# PCB_1.net
KiCad netlist of a schematic drawn in EAGLE
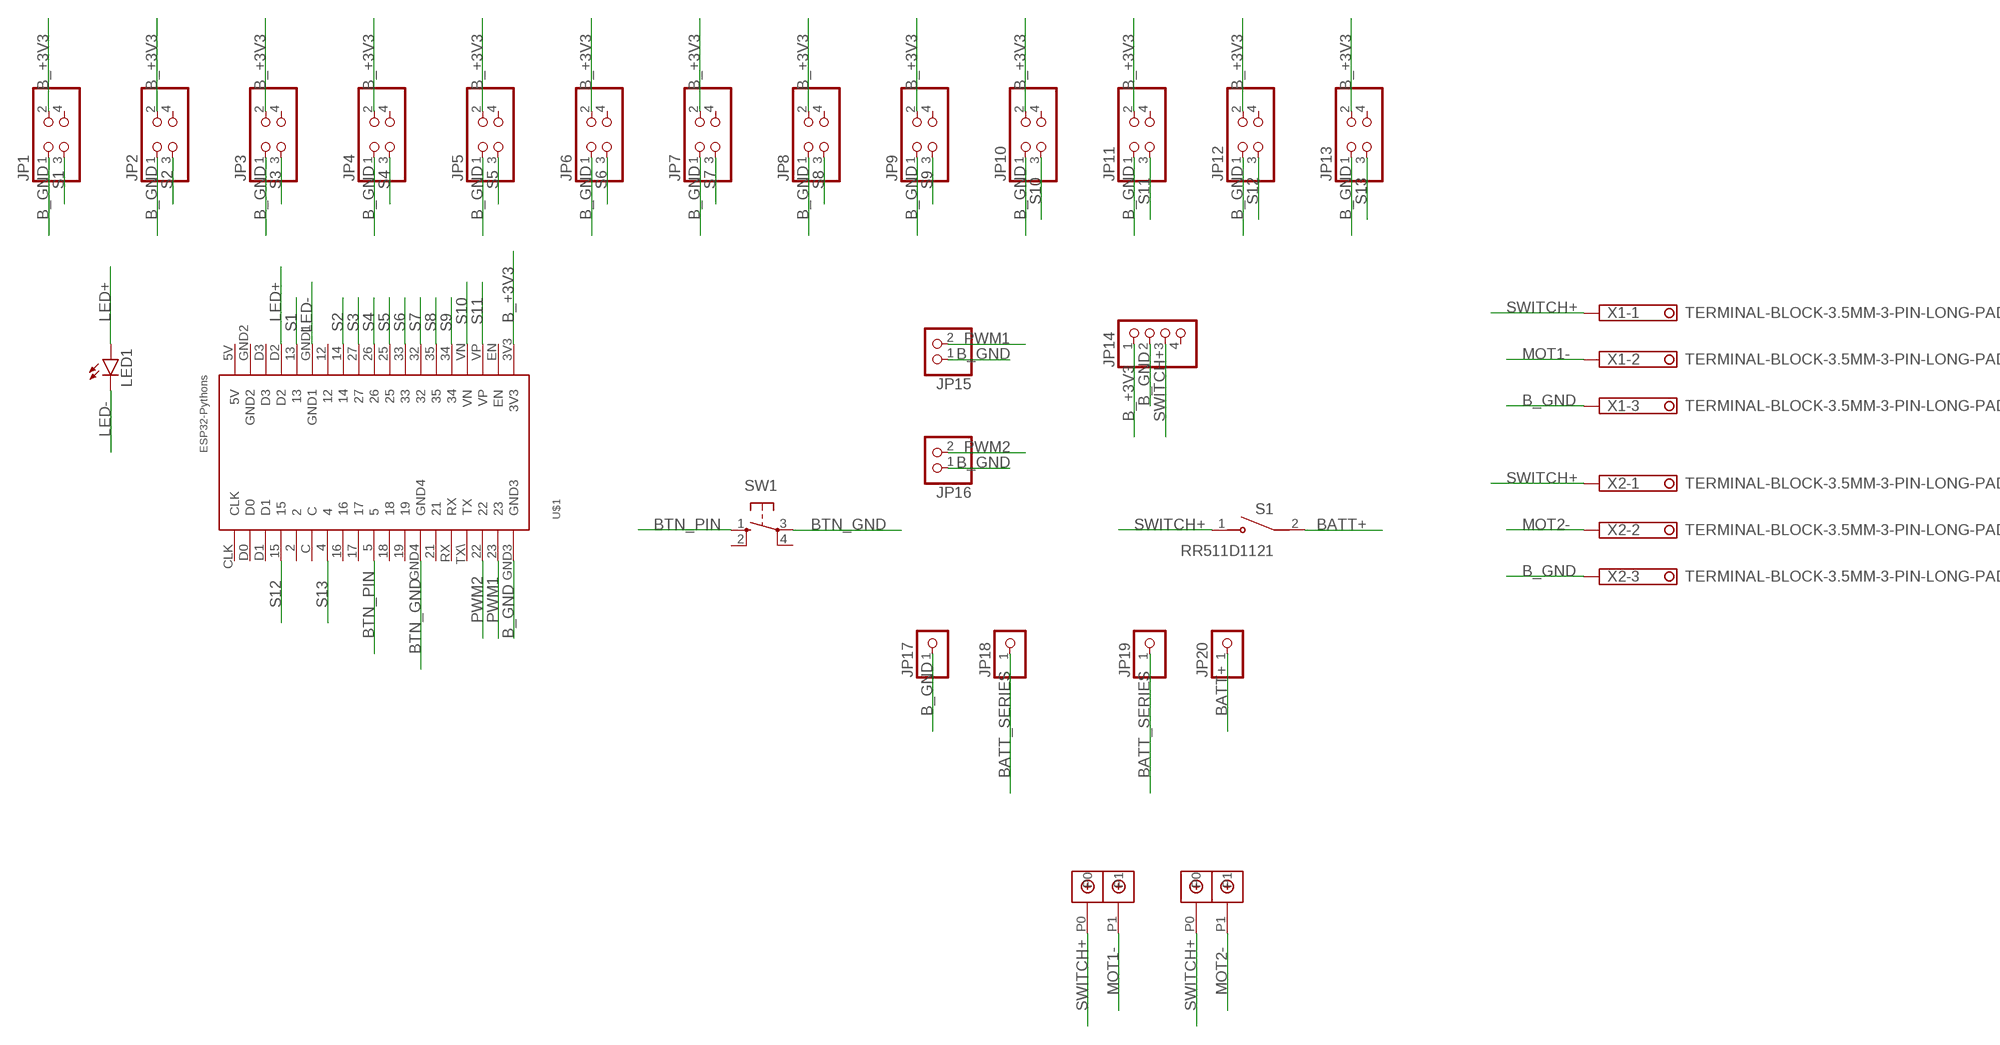
[diagram p0: schematic, sheet 1]

(export (version "E")
  (design (tool "Eeschema 10.0.6"))
  (components
    (comp (ref "JP1")
      (value "PINHD-2X2")
      (footprint "eagle-import:2X02")
      (libsource (lib "eagle-import") (part "PINHD-2X2"))
    )
    (comp (ref "JP2")
      (value "PINHD-2X2")
      (footprint "eagle-import:2X02")
      (libsource (lib "eagle-import") (part "PINHD-2X2"))
    )
    (comp (ref "JP3")
      (value "PINHD-2X2")
      (footprint "eagle-import:2X02")
      (libsource (lib "eagle-import") (part "PINHD-2X2"))
    )
    (comp (ref "JP4")
      (value "PINHD-2X2")
      (footprint "eagle-import:2X02")
      (libsource (lib "eagle-import") (part "PINHD-2X2"))
    )
    (comp (ref "JP5")
      (value "PINHD-2X2")
      (footprint "eagle-import:2X02")
      (libsource (lib "eagle-import") (part "PINHD-2X2"))
    )
    (comp (ref "JP6")
      (value "PINHD-2X2")
      (footprint "eagle-import:2X02")
      (libsource (lib "eagle-import") (part "PINHD-2X2"))
    )
    (comp (ref "JP7")
      (value "PINHD-2X2")
      (footprint "eagle-import:2X02")
      (libsource (lib "eagle-import") (part "PINHD-2X2"))
    )
    (comp (ref "JP8")
      (value "PINHD-2X2")
      (footprint "eagle-import:2X02")
      (libsource (lib "eagle-import") (part "PINHD-2X2"))
    )
    (comp (ref "JP9")
      (value "PINHD-2X2")
      (footprint "eagle-import:2X02")
      (libsource (lib "eagle-import") (part "PINHD-2X2"))
    )
    (comp (ref "JP10")
      (value "PINHD-2X2")
      (footprint "eagle-import:2X02")
      (libsource (lib "eagle-import") (part "PINHD-2X2"))
    )
    (comp (ref "JP11")
      (value "PINHD-2X2")
      (footprint "eagle-import:2X02")
      (libsource (lib "eagle-import") (part "PINHD-2X2"))
    )
    (comp (ref "JP12")
      (value "PINHD-2X2")
      (footprint "eagle-import:2X02")
      (libsource (lib "eagle-import") (part "PINHD-2X2"))
    )
    (comp (ref "JP13")
      (value "PINHD-2X2")
      (footprint "eagle-import:2X02")
      (libsource (lib "eagle-import") (part "PINHD-2X2"))
    )
    (comp (ref "JP14")
      (value "PINHD-1X4")
      (footprint "eagle-import:1X04")
      (libsource (lib "eagle-import") (part "PINHD-1X4"))
    )
    (comp (ref "JP15")
      (value "PINHD-1X2")
      (footprint "eagle-import:1X02")
      (libsource (lib "eagle-import") (part "PINHD-1X2"))
    )
    (comp (ref "JP16")
      (value "PINHD-1X2")
      (footprint "eagle-import:1X02")
      (libsource (lib "eagle-import") (part "PINHD-1X2"))
    )
    (comp (ref "JP17")
      (value "PINHD-1X1")
      (footprint "eagle-import:1X01")
      (libsource (lib "eagle-import") (part "PINHD-1X1"))
    )
    (comp (ref "JP18")
      (value "PINHD-1X1")
      (footprint "eagle-import:1X01")
      (libsource (lib "eagle-import") (part "PINHD-1X1"))
    )
    (comp (ref "JP19")
      (value "PINHD-1X1")
      (footprint "eagle-import:1X01")
      (libsource (lib "eagle-import") (part "PINHD-1X1"))
    )
    (comp (ref "JP20")
      (value "PINHD-1X1")
      (footprint "eagle-import:1X01")
      (libsource (lib "eagle-import") (part "PINHD-1X1"))
    )
    (comp (ref "LED1")
      (value "LED5MM")
      (footprint "eagle-import:LED5MM")
      (libsource (lib "eagle-import") (part "LED5MM"))
    )
    (comp (ref "S1")
      (value "RR511D1121")
      (footprint "eagle-import:E-SWITCH_RR511D1121")
      (fields (field (name "MF") "E-Switch"))
      (libsource (lib "eagle-import") (part "RR511D1121"))
    )
    (comp (ref "SW1")
      (value "10-XX")
      (footprint "eagle-import:B3F-10XX")
      (libsource (lib "eagle-import") (part "10-XX"))
    )
    (comp (ref "U$1")
      (value "ESP32DEVKITV1")
      (footprint "eagle-import:ESP32-DEVKITV1")
      (libsource (lib "eagle-import") (part "ESP32DEVKITV1"))
    )
    (comp (ref "U$2")
      (value "DBCONN-1X2")
      (footprint "eagle-import:DBCONN-1X2")
      (libsource (lib "eagle-import") (part "DBCONN-1X2"))
    )
    (comp (ref "U$3")
      (value "DBCONN-1X2")
      (footprint "eagle-import:DBCONN-1X2")
      (libsource (lib "eagle-import") (part "DBCONN-1X2"))
    )
    (comp (ref "X1")
      (value "TERMINAL-BLOCK-3.5MM-3-PIN-LONG-PAD")
      (footprint "eagle-import:TERMINAL-BLOCK-3-PIN-3.5MM-LONG-PAD")
      (libsource (lib "eagle-import") (part "TERMINAL-BLOCK-3.5MM-3-PIN-LONG-PAD"))
    )
    (comp (ref "X2")
      (value "TERMINAL-BLOCK-3.5MM-3-PIN-LONG-PAD")
      (footprint "eagle-import:TERMINAL-BLOCK-3-PIN-3.5MM-LONG-PAD")
      (libsource (lib "eagle-import") (part "TERMINAL-BLOCK-3.5MM-3-PIN-LONG-PAD"))
    )
  )
  (nets
    (net (code "1") (name "/BATT+") (class "Default")
      (node (ref "JP20") (pin "1") (pinfunction "1_1") (pintype "passive"))
      (node (ref "S1") (pin "2") (pinfunction "COM_2") (pintype "passive"))
    )
    (net (code "2") (name "/BATT_SERIES") (class "Default")
      (node (ref "JP18") (pin "1") (pinfunction "1_1") (pintype "passive"))
      (node (ref "JP19") (pin "1") (pinfunction "1_1") (pintype "passive"))
    )
    (net (code "3") (name "/BTN_GND") (class "Default")
      (node (ref "SW1") (pin "3") (pinfunction "P_3") (pintype "passive"))
      (node (ref "U$1") (pin "GND4") (pinfunction "GND4_GND4") (pintype "bidirectional"))
    )
    (net (code "4") (name "/BTN_PIN") (class "Default")
      (node (ref "SW1") (pin "1") (pinfunction "S_1") (pintype "passive"))
      (node (ref "U$1") (pin "5") (pinfunction "5_5") (pintype "bidirectional"))
    )
    (net (code "5") (name "/B_+3V3") (class "Default")
      (node (ref "JP1") (pin "2") (pinfunction "2_2") (pintype "passive"))
      (node (ref "JP10") (pin "2") (pinfunction "2_2") (pintype "passive"))
      (node (ref "JP11") (pin "2") (pinfunction "2_2") (pintype "passive"))
      (node (ref "JP12") (pin "2") (pinfunction "2_2") (pintype "passive"))
      (node (ref "JP13") (pin "2") (pinfunction "2_2") (pintype "passive"))
      (node (ref "JP14") (pin "1") (pinfunction "1_1") (pintype "passive"))
      (node (ref "JP2") (pin "2") (pinfunction "2_2") (pintype "passive"))
      (node (ref "JP3") (pin "2") (pinfunction "2_2") (pintype "passive"))
      (node (ref "JP4") (pin "2") (pinfunction "2_2") (pintype "passive"))
      (node (ref "JP5") (pin "2") (pinfunction "2_2") (pintype "passive"))
      (node (ref "JP6") (pin "2") (pinfunction "2_2") (pintype "passive"))
      (node (ref "JP7") (pin "2") (pinfunction "2_2") (pintype "passive"))
      (node (ref "JP8") (pin "2") (pinfunction "2_2") (pintype "passive"))
      (node (ref "JP9") (pin "2") (pinfunction "2_2") (pintype "passive"))
      (node (ref "U$1") (pin "3V3") (pinfunction "3V3_3V3") (pintype "bidirectional"))
    )
    (net (code "6") (name "/B_GND") (class "Default")
      (node (ref "JP1") (pin "1") (pinfunction "1_1") (pintype "passive"))
      (node (ref "JP10") (pin "1") (pinfunction "1_1") (pintype "passive"))
      (node (ref "JP11") (pin "1") (pinfunction "1_1") (pintype "passive"))
      (node (ref "JP12") (pin "1") (pinfunction "1_1") (pintype "passive"))
      (node (ref "JP13") (pin "1") (pinfunction "1_1") (pintype "passive"))
      (node (ref "JP14") (pin "2") (pinfunction "2_2") (pintype "passive"))
      (node (ref "JP15") (pin "1") (pinfunction "1_1") (pintype "passive"))
      (node (ref "JP16") (pin "1") (pinfunction "1_1") (pintype "passive"))
      (node (ref "JP17") (pin "1") (pinfunction "1_1") (pintype "passive"))
      (node (ref "JP2") (pin "1") (pinfunction "1_1") (pintype "passive"))
      (node (ref "JP3") (pin "1") (pinfunction "1_1") (pintype "passive"))
      (node (ref "JP4") (pin "1") (pinfunction "1_1") (pintype "passive"))
      (node (ref "JP5") (pin "1") (pinfunction "1_1") (pintype "passive"))
      (node (ref "JP6") (pin "1") (pinfunction "1_1") (pintype "passive"))
      (node (ref "JP7") (pin "1") (pinfunction "1_1") (pintype "passive"))
      (node (ref "JP8") (pin "1") (pinfunction "1_1") (pintype "passive"))
      (node (ref "JP9") (pin "1") (pinfunction "1_1") (pintype "passive"))
      (node (ref "U$1") (pin "GND3") (pinfunction "GND3_GND3") (pintype "bidirectional"))
      (node (ref "X1") (pin "3") (pinfunction "K_3") (pintype "passive"))
      (node (ref "X2") (pin "3") (pinfunction "K_3") (pintype "passive"))
    )
    (net (code "7") (name "/LED+") (class "Default")
      (node (ref "LED1") (pin "A") (pinfunction "A_A") (pintype "passive"))
      (node (ref "U$1") (pin "D2") (pinfunction "D2_D2") (pintype "bidirectional"))
    )
    (net (code "8") (name "/LED-") (class "Default")
      (node (ref "LED1") (pin "K") (pinfunction "C_K") (pintype "passive"))
      (node (ref "U$1") (pin "GND1") (pinfunction "GND1_GND1") (pintype "bidirectional"))
    )
    (net (code "9") (name "/MOT1-") (class "Default")
      (node (ref "U$2") (pin "P1") (pinfunction "P1_P1") (pintype "bidirectional"))
      (node (ref "X1") (pin "2") (pinfunction "K_2") (pintype "passive"))
    )
    (net (code "10") (name "/MOT2-") (class "Default")
      (node (ref "U$3") (pin "P1") (pinfunction "P1_P1") (pintype "bidirectional"))
      (node (ref "X2") (pin "2") (pinfunction "K_2") (pintype "passive"))
    )
    (net (code "11") (name "/PWM1") (class "Default")
      (node (ref "JP15") (pin "2") (pinfunction "2_2") (pintype "passive"))
      (node (ref "U$1") (pin "23") (pinfunction "23_23") (pintype "bidirectional"))
    )
    (net (code "12") (name "/PWM2") (class "Default")
      (node (ref "JP16") (pin "2") (pinfunction "2_2") (pintype "passive"))
      (node (ref "U$1") (pin "22") (pinfunction "22_22") (pintype "bidirectional"))
    )
    (net (code "13") (name "/S1") (class "Default")
      (node (ref "JP1") (pin "3") (pinfunction "3_3") (pintype "passive"))
      (node (ref "U$1") (pin "13") (pinfunction "13_13") (pintype "bidirectional"))
    )
    (net (code "14") (name "/S2") (class "Default")
      (node (ref "JP2") (pin "3") (pinfunction "3_3") (pintype "passive"))
      (node (ref "U$1") (pin "14") (pinfunction "14_14") (pintype "bidirectional"))
    )
    (net (code "15") (name "/S3") (class "Default")
      (node (ref "JP3") (pin "3") (pinfunction "3_3") (pintype "passive"))
      (node (ref "U$1") (pin "27") (pinfunction "27_27") (pintype "bidirectional"))
    )
    (net (code "16") (name "/S4") (class "Default")
      (node (ref "JP4") (pin "3") (pinfunction "3_3") (pintype "passive"))
      (node (ref "U$1") (pin "26") (pinfunction "26_26") (pintype "bidirectional"))
    )
    (net (code "17") (name "/S5") (class "Default")
      (node (ref "JP5") (pin "3") (pinfunction "3_3") (pintype "passive"))
      (node (ref "U$1") (pin "25") (pinfunction "25_25") (pintype "bidirectional"))
    )
    (net (code "18") (name "/S6") (class "Default")
      (node (ref "JP6") (pin "3") (pinfunction "3_3") (pintype "passive"))
      (node (ref "U$1") (pin "33") (pinfunction "33_33") (pintype "bidirectional"))
    )
    (net (code "19") (name "/S7") (class "Default")
      (node (ref "JP7") (pin "3") (pinfunction "3_3") (pintype "passive"))
      (node (ref "U$1") (pin "32") (pinfunction "32_32") (pintype "bidirectional"))
    )
    (net (code "20") (name "/S8") (class "Default")
      (node (ref "JP8") (pin "3") (pinfunction "3_3") (pintype "passive"))
      (node (ref "U$1") (pin "35") (pinfunction "35_35") (pintype "bidirectional"))
    )
    (net (code "21") (name "/S9") (class "Default")
      (node (ref "JP9") (pin "3") (pinfunction "3_3") (pintype "passive"))
      (node (ref "U$1") (pin "34") (pinfunction "34_34") (pintype "bidirectional"))
    )
    (net (code "22") (name "/S10") (class "Default")
      (node (ref "JP10") (pin "3") (pinfunction "3_3") (pintype "passive"))
      (node (ref "U$1") (pin "VN") (pinfunction "VN_VN") (pintype "bidirectional"))
    )
    (net (code "23") (name "/S11") (class "Default")
      (node (ref "JP11") (pin "3") (pinfunction "3_3") (pintype "passive"))
      (node (ref "U$1") (pin "VP") (pinfunction "VP_VP") (pintype "bidirectional"))
    )
    (net (code "24") (name "/S12") (class "Default")
      (node (ref "JP12") (pin "3") (pinfunction "3_3") (pintype "passive"))
      (node (ref "U$1") (pin "15") (pinfunction "15_15") (pintype "bidirectional"))
    )
    (net (code "25") (name "/S13") (class "Default")
      (node (ref "JP13") (pin "3") (pinfunction "3_3") (pintype "passive"))
      (node (ref "U$1") (pin "4") (pinfunction "4_4") (pintype "bidirectional"))
    )
    (net (code "26") (name "/SWITCH+") (class "Default")
      (node (ref "JP14") (pin "3") (pinfunction "3_3") (pintype "passive"))
      (node (ref "S1") (pin "1") (pinfunction "NO_1") (pintype "passive"))
      (node (ref "U$2") (pin "P0") (pinfunction "P0_P0") (pintype "bidirectional"))
      (node (ref "U$3") (pin "P0") (pinfunction "P0_P0") (pintype "bidirectional"))
      (node (ref "X1") (pin "1") (pinfunction "K_1") (pintype "passive"))
      (node (ref "X2") (pin "1") (pinfunction "K_1") (pintype "passive"))
    )
    (net (code "27") (name "unconnected-(JP1-Pad4)") (class "Default")
      (node (ref "JP1") (pin "4") (pinfunction "4_4") (pintype "passive"))
    )
    (net (code "28") (name "unconnected-(JP2-Pad4)") (class "Default")
      (node (ref "JP2") (pin "4") (pinfunction "4_4") (pintype "passive"))
    )
    (net (code "29") (name "unconnected-(JP3-Pad4)") (class "Default")
      (node (ref "JP3") (pin "4") (pinfunction "4_4") (pintype "passive"))
    )
    (net (code "30") (name "unconnected-(JP4-Pad4)") (class "Default")
      (node (ref "JP4") (pin "4") (pinfunction "4_4") (pintype "passive"))
    )
    (net (code "31") (name "unconnected-(JP5-Pad4)") (class "Default")
      (node (ref "JP5") (pin "4") (pinfunction "4_4") (pintype "passive"))
    )
    (net (code "32") (name "unconnected-(JP6-Pad4)") (class "Default")
      (node (ref "JP6") (pin "4") (pinfunction "4_4") (pintype "passive"))
    )
    (net (code "33") (name "unconnected-(JP7-Pad4)") (class "Default")
      (node (ref "JP7") (pin "4") (pinfunction "4_4") (pintype "passive"))
    )
    (net (code "34") (name "unconnected-(JP8-Pad4)") (class "Default")
      (node (ref "JP8") (pin "4") (pinfunction "4_4") (pintype "passive"))
    )
    (net (code "35") (name "unconnected-(JP9-Pad4)") (class "Default")
      (node (ref "JP9") (pin "4") (pinfunction "4_4") (pintype "passive"))
    )
    (net (code "36") (name "unconnected-(JP10-Pad4)") (class "Default")
      (node (ref "JP10") (pin "4") (pinfunction "4_4") (pintype "passive"))
    )
    (net (code "37") (name "unconnected-(JP11-Pad4)") (class "Default")
      (node (ref "JP11") (pin "4") (pinfunction "4_4") (pintype "passive"))
    )
    (net (code "38") (name "unconnected-(JP12-Pad4)") (class "Default")
      (node (ref "JP12") (pin "4") (pinfunction "4_4") (pintype "passive"))
    )
    (net (code "39") (name "unconnected-(JP13-Pad4)") (class "Default")
      (node (ref "JP13") (pin "4") (pinfunction "4_4") (pintype "passive"))
    )
    (net (code "40") (name "unconnected-(JP14-Pad4)") (class "Default")
      (node (ref "JP14") (pin "4") (pinfunction "4_4") (pintype "passive"))
    )
    (net (code "41") (name "unconnected-(SW1-P1-Pad4)") (class "Default")
      (node (ref "SW1") (pin "4") (pinfunction "P1_4") (pintype "passive"))
    )
    (net (code "42") (name "unconnected-(SW1-S1-Pad2)") (class "Default")
      (node (ref "SW1") (pin "2") (pinfunction "S1_2") (pintype "passive"))
    )
    (net (code "43") (name "unconnected-(U$1-Pad2)") (class "Default")
      (node (ref "U$1") (pin "2") (pinfunction "2_2") (pintype "bidirectional"))
    )
    (net (code "44") (name "unconnected-(U$1-Pad5V)") (class "Default")
      (node (ref "U$1") (pin "5V") (pinfunction "5V_5V") (pintype "bidirectional"))
    )
    (net (code "45") (name "unconnected-(U$1-Pad12)") (class "Default")
      (node (ref "U$1") (pin "12") (pinfunction "12_12") (pintype "bidirectional"))
    )
    (net (code "46") (name "unconnected-(U$1-Pad16)") (class "Default")
      (node (ref "U$1") (pin "16") (pinfunction "16_16") (pintype "bidirectional"))
    )
    (net (code "47") (name "unconnected-(U$1-Pad17)") (class "Default")
      (node (ref "U$1") (pin "17") (pinfunction "17_17") (pintype "bidirectional"))
    )
    (net (code "48") (name "unconnected-(U$1-Pad18)") (class "Default")
      (node (ref "U$1") (pin "18") (pinfunction "18_18") (pintype "bidirectional"))
    )
    (net (code "49") (name "unconnected-(U$1-Pad19)") (class "Default")
      (node (ref "U$1") (pin "19") (pinfunction "19_19") (pintype "bidirectional"))
    )
    (net (code "50") (name "unconnected-(U$1-Pad21)") (class "Default")
      (node (ref "U$1") (pin "21") (pinfunction "21_21") (pintype "bidirectional"))
    )
    (net (code "51") (name "unconnected-(U$1-PadC)") (class "Default")
      (node (ref "U$1") (pin "C") (pinfunction "C_C") (pintype "bidirectional"))
    )
    (net (code "52") (name "unconnected-(U$1-PadCLK)") (class "Default")
      (node (ref "U$1") (pin "CLK") (pinfunction "CLK_CLK") (pintype "bidirectional"))
    )
    (net (code "53") (name "unconnected-(U$1-PadD0)") (class "Default")
      (node (ref "U$1") (pin "D0") (pinfunction "D0_D0") (pintype "bidirectional"))
    )
    (net (code "54") (name "unconnected-(U$1-PadD1)") (class "Default")
      (node (ref "U$1") (pin "D1") (pinfunction "D1_D1") (pintype "bidirectional"))
    )
    (net (code "55") (name "unconnected-(U$1-PadD3)") (class "Default")
      (node (ref "U$1") (pin "D3") (pinfunction "D3_D3") (pintype "bidirectional"))
    )
    (net (code "56") (name "unconnected-(U$1-PadEN)") (class "Default")
      (node (ref "U$1") (pin "EN") (pinfunction "EN_EN") (pintype "bidirectional"))
    )
    (net (code "57") (name "unconnected-(U$1-PadGND2)") (class "Default")
      (node (ref "U$1") (pin "GND2") (pinfunction "GND2_GND2") (pintype "bidirectional"))
    )
    (net (code "58") (name "unconnected-(U$1-PadRX)") (class "Default")
      (node (ref "U$1") (pin "RX") (pinfunction "RX_RX") (pintype "bidirectional"))
    )
    (net (code "59") (name "unconnected-(U$1-TX-PadTX\\)") (class "Default")
      (node (ref "U$1") (pin "TX\\") (pinfunction "TX_TX\\") (pintype "bidirectional"))
    )
  )
)
